# PlanktoscopeHat-v0_2-fab.net
KiCad netlist of a schematic drawn in EAGLE
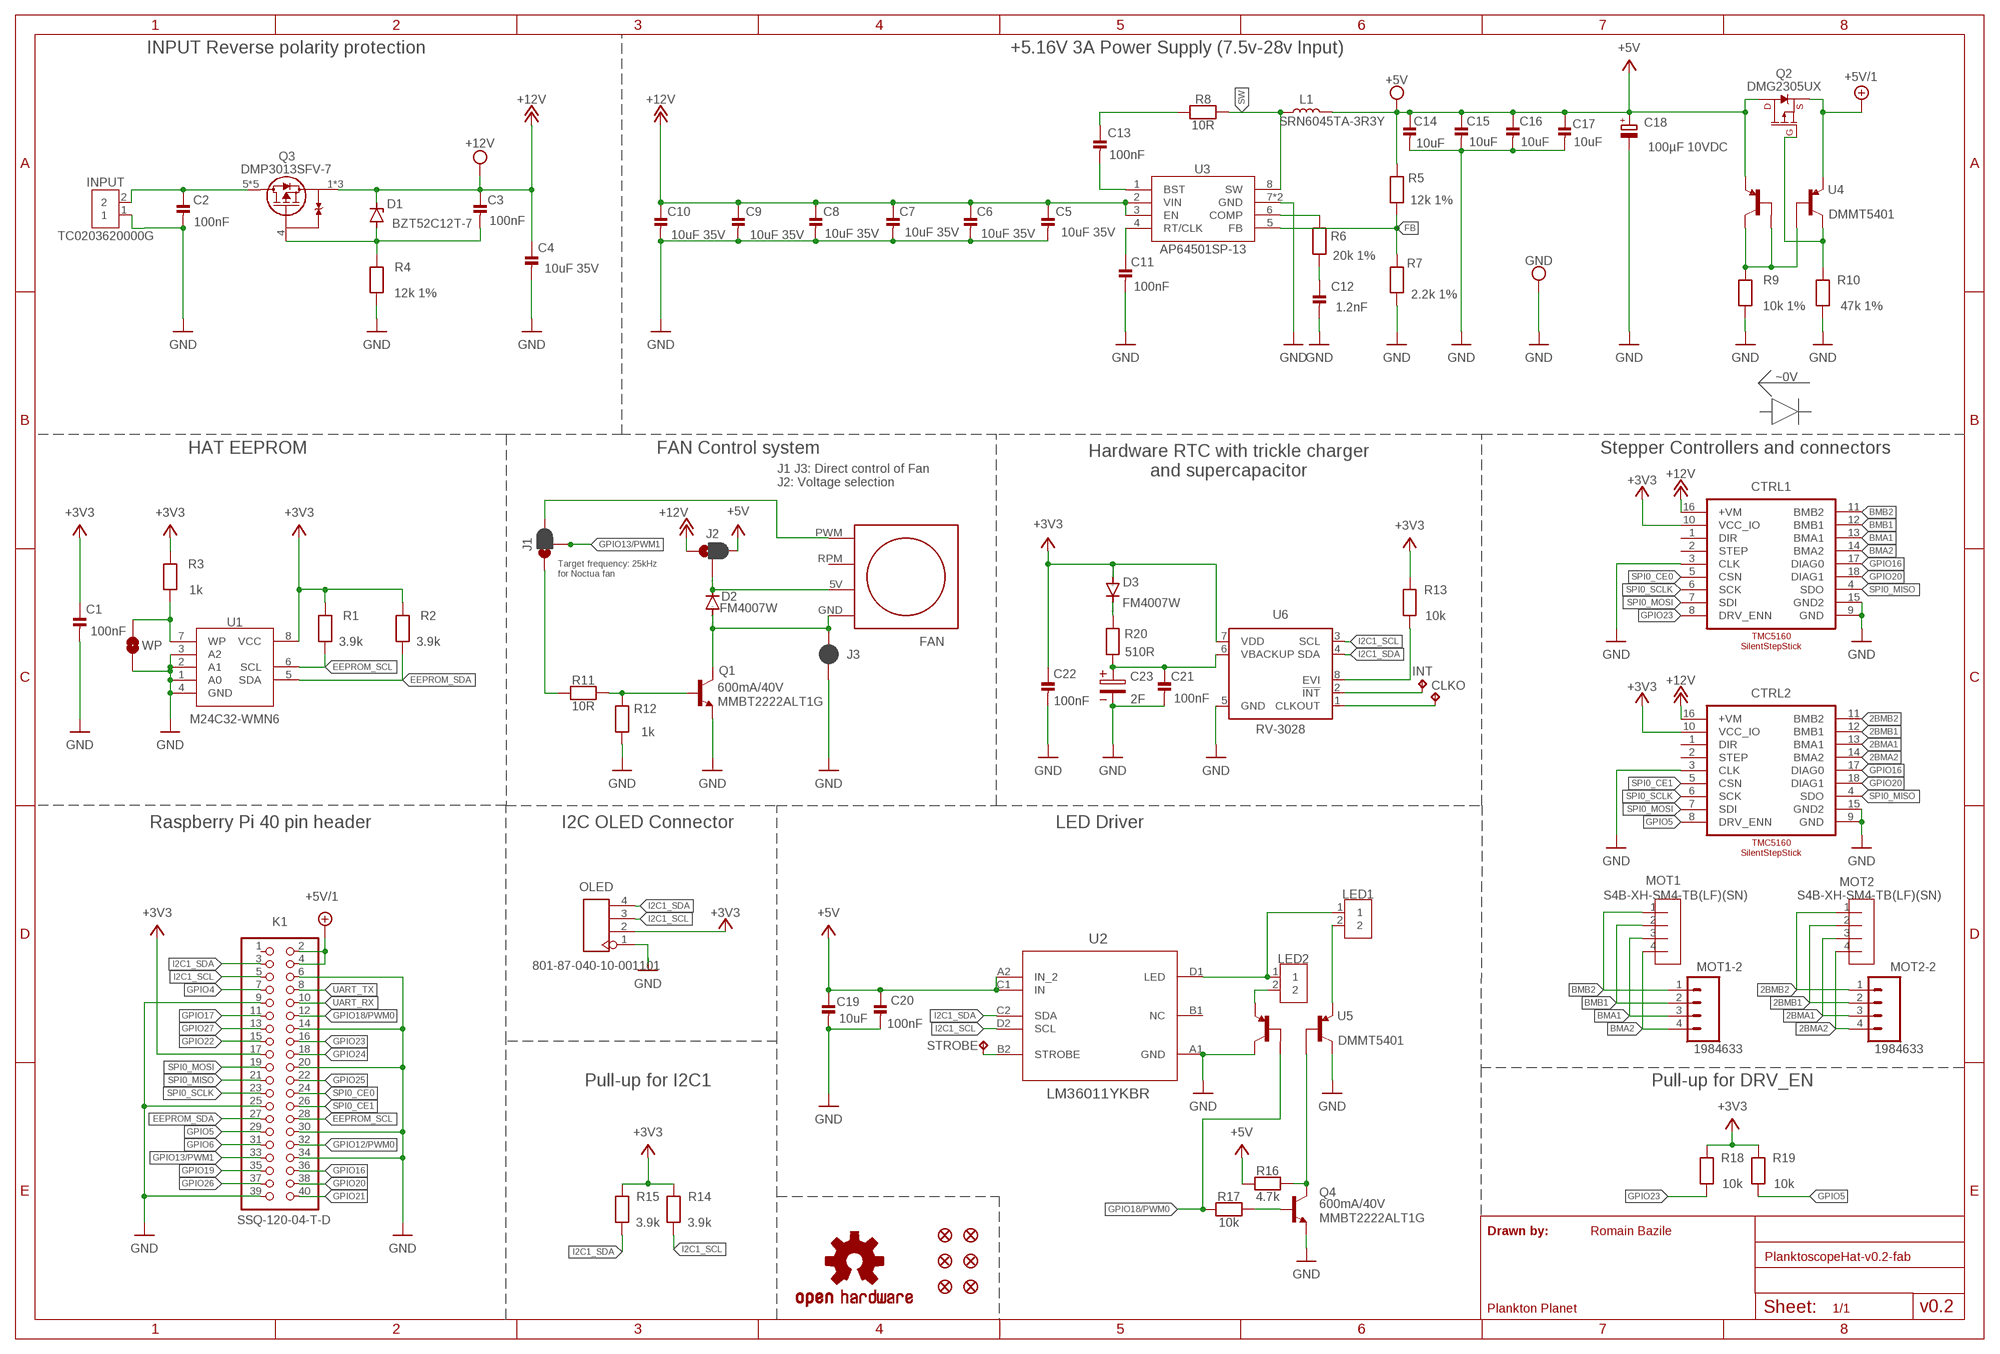
[diagram p0: schematic, sheet 1]

(export (version "E")
  (design (tool "Eeschema 10.0.6"))
  (components
    (comp (ref "+5V")
      (value "TESTPOINTPAD2MM")
      (footprint "eagle-import:TESTPOINT_PAD_2MM")
      (libsource (lib "eagle-import") (part "TESTPOINTPAD2MM"))
    )
    (comp (ref "+12V")
      (value "TESTPOINTPAD2MM")
      (footprint "eagle-import:TESTPOINT_PAD_2MM")
      (libsource (lib "eagle-import") (part "TESTPOINTPAD2MM"))
    )
    (comp (ref "C1")
      (value "100nF")
      (footprint "eagle-import:_0805MP")
      (libsource (lib "eagle-import") (part "CAP_CERAMIC_0805MP"))
    )
    (comp (ref "C2")
      (value "100nF")
      (footprint "eagle-import:_0805MP")
      (libsource (lib "eagle-import") (part "CAP_CERAMIC_0805MP"))
    )
    (comp (ref "C3")
      (value "100nF")
      (footprint "eagle-import:_0805MP")
      (libsource (lib "eagle-import") (part "CAP_CERAMIC_0805MP"))
    )
    (comp (ref "C4")
      (value "10uF 35V")
      (footprint "eagle-import:_0805MP")
      (libsource (lib "eagle-import") (part "CAP_CERAMIC_0805MP"))
    )
    (comp (ref "C5")
      (value "10uF 35V")
      (footprint "eagle-import:_0805MP")
      (libsource (lib "eagle-import") (part "CAP_CERAMIC_0805MP"))
    )
    (comp (ref "C6")
      (value "10uF 35V")
      (footprint "eagle-import:_0805MP")
      (libsource (lib "eagle-import") (part "CAP_CERAMIC_0805MP"))
    )
    (comp (ref "C7")
      (value "10uF 35V")
      (footprint "eagle-import:_0805MP")
      (libsource (lib "eagle-import") (part "CAP_CERAMIC_0805MP"))
    )
    (comp (ref "C8")
      (value "10uF 35V")
      (footprint "eagle-import:_0805MP")
      (libsource (lib "eagle-import") (part "CAP_CERAMIC_0805MP"))
    )
    (comp (ref "C9")
      (value "10uF 35V")
      (footprint "eagle-import:_0805MP")
      (libsource (lib "eagle-import") (part "CAP_CERAMIC_0805MP"))
    )
    (comp (ref "C10")
      (value "10uF 35V")
      (footprint "eagle-import:_0805MP")
      (libsource (lib "eagle-import") (part "CAP_CERAMIC_0805MP"))
    )
    (comp (ref "C11")
      (value "100nF")
      (footprint "eagle-import:_0805MP")
      (libsource (lib "eagle-import") (part "CAP_CERAMIC_0805MP"))
    )
    (comp (ref "C12")
      (value "1.2nF")
      (footprint "eagle-import:_0805MP")
      (libsource (lib "eagle-import") (part "CAP_CERAMIC_0805MP"))
    )
    (comp (ref "C13")
      (value "100nF")
      (footprint "eagle-import:_0805MP")
      (libsource (lib "eagle-import") (part "CAP_CERAMIC_0805MP"))
    )
    (comp (ref "C14")
      (value "10uF")
      (footprint "eagle-import:_0805MP")
      (libsource (lib "eagle-import") (part "CAP_CERAMIC_0805MP"))
    )
    (comp (ref "C15")
      (value "10uF")
      (footprint "eagle-import:_0805MP")
      (libsource (lib "eagle-import") (part "CAP_CERAMIC_0805MP"))
    )
    (comp (ref "C16")
      (value "10uF")
      (footprint "eagle-import:_0805MP")
      (libsource (lib "eagle-import") (part "CAP_CERAMIC_0805MP"))
    )
    (comp (ref "C17")
      (value "10uF")
      (footprint "eagle-import:_0805MP")
      (libsource (lib "eagle-import") (part "CAP_CERAMIC_0805MP"))
    )
    (comp (ref "C18")
      (value "100µF 10VDC")
      (footprint "eagle-import:CAPMP6032X280N")
      (fields (field (name "MPN") "TPSC107K010T0200"))
      (libsource (lib "eagle-import") (part "C-POLTANTALUM-2412(6032-METRIC)_"))
    )
    (comp (ref "C19")
      (value "10uF")
      (footprint "eagle-import:_0805MP")
      (libsource (lib "eagle-import") (part "CAP_CERAMIC_0805MP"))
    )
    (comp (ref "C20")
      (value "100nF")
      (footprint "eagle-import:_0805MP")
      (libsource (lib "eagle-import") (part "CAP_CERAMIC_0805MP"))
    )
    (comp (ref "C21")
      (value "100nF")
      (footprint "eagle-import:_0805MP")
      (libsource (lib "eagle-import") (part "CAP_CERAMIC_0805MP"))
    )
    (comp (ref "C22")
      (value "100nF")
      (footprint "eagle-import:_0805MP")
      (libsource (lib "eagle-import") (part "CAP_CERAMIC_0805MP"))
    )
    (comp (ref "C23")
      (value "2F")
      (footprint "eagle-import:8X3.5X0.9(DXAXB)")
      (fields (field (name "MPN") "SCCR12E105SRB"))
      (libsource (lib "eagle-import") (part "WCAP-PTHT_870135174001_8X8"))
    )
    (comp (ref "CLKO")
      (value "TPB1,27")
      (footprint "eagle-import:B1,27")
      (libsource (lib "eagle-import") (part "TPB1,27"))
    )
    (comp (ref "CTRL1")
      (value "TMC5160_SILENTSTEPSTICK")
      (footprint "eagle-import:TMC5160_STEPSTICK")
      (libsource (lib "eagle-import") (part "TMC5160_SILENTSTEPSTICK"))
    )
    (comp (ref "CTRL2")
      (value "TMC5160_SILENTSTEPSTICK")
      (footprint "eagle-import:TMC5160_STEPSTICK")
      (libsource (lib "eagle-import") (part "TMC5160_SILENTSTEPSTICK"))
    )
    (comp (ref "D1")
      (value "BZT52C12T-7")
      (footprint "eagle-import:SODFL1608X70")
      (libsource (lib "eagle-import") (part "ZENERSODFL(1608-METRIC)_"))
    )
    (comp (ref "D2")
      (value "FM4007W")
      (footprint "eagle-import:DO-214AC")
      (libsource (lib "eagle-import") (part "DIODE-DO-214AC"))
    )
    (comp (ref "D3")
      (value "FM4007W")
      (footprint "eagle-import:DO-214AC")
      (libsource (lib "eagle-import") (part "DIODE-DO-214AC"))
    )
    (comp (ref "FAN")
      (value "40MM_FAN")
      (footprint "eagle-import:40MM_FAN")
      (libsource (lib "eagle-import") (part "40MM_FAN"))
    )
    (comp (ref "FD1")
      (value "FIDUCIAL1X2")
      (footprint "eagle-import:FIDUCIAL-1X2")
      (libsource (lib "eagle-import") (part "FIDUCIAL1X2"))
    )
    (comp (ref "FD2")
      (value "FIDUCIAL1X2")
      (footprint "eagle-import:FIDUCIAL-1X2")
      (libsource (lib "eagle-import") (part "FIDUCIAL1X2"))
    )
    (comp (ref "FD3")
      (value "FIDUCIAL1X2")
      (footprint "eagle-import:FIDUCIAL-1X2")
      (libsource (lib "eagle-import") (part "FIDUCIAL1X2"))
    )
    (comp (ref "FD4")
      (value "FIDUCIAL1X2")
      (footprint "eagle-import:FIDUCIAL-1X2")
      (libsource (lib "eagle-import") (part "FIDUCIAL1X2"))
    )
    (comp (ref "FD5")
      (value "FIDUCIAL1X2")
      (footprint "eagle-import:FIDUCIAL-1X2")
      (libsource (lib "eagle-import") (part "FIDUCIAL1X2"))
    )
    (comp (ref "FD6")
      (value "FIDUCIAL1X2")
      (footprint "eagle-import:FIDUCIAL-1X2")
      (libsource (lib "eagle-import") (part "FIDUCIAL1X2"))
    )
    (comp (ref "GND")
      (value "TESTPOINTPAD2MM")
      (footprint "eagle-import:TESTPOINT_PAD_2MM")
      (libsource (lib "eagle-import") (part "TESTPOINTPAD2MM"))
    )
    (comp (ref "INPUT")
      (value "TC0203620000G")
      (footprint "eagle-import:TERMBLK_508-2N")
      (fields
        (field (name "MANUFACTURER") "TE Connectivity")
        (field (name "MPN") "282837-2")
        (field (name "MPN_1") "TC0203620000G")
      )
      (libsource (lib "eagle-import") (part "2828XX-2282837-2"))
    )
    (comp (ref "INT")
      (value "TPB1,27")
      (footprint "eagle-import:B1,27")
      (libsource (lib "eagle-import") (part "TPB1,27"))
    )
    (comp (ref "J1")
      (value "JUMPER-SMT_3_1-NC_PASTE_SILK")
      (footprint "eagle-import:SMT-JUMPER_3_1-NC_PASTE_SILK")
      (libsource (lib "eagle-import") (part "JUMPER-SMT_3_1-NC_PASTE_SILK"))
    )
    (comp (ref "J2")
      (value "JUMPER-SMT_3_1-NC_PASTE_SILK")
      (footprint "eagle-import:SMT-JUMPER_3_1-NC_PASTE_SILK")
      (libsource (lib "eagle-import") (part "JUMPER-SMT_3_1-NC_PASTE_SILK"))
    )
    (comp (ref "J3")
      (value "JUMPER-SMT_2_NC_PASTE_SILK")
      (footprint "eagle-import:SMT-JUMPER_2_NC_PASTE_SILK")
      (libsource (lib "eagle-import") (part "JUMPER-SMT_2_NC_PASTE_SILK"))
    )
    (comp (ref "K1")
      (value "SSQ-120-04-T-D")
      (footprint "eagle-import:2X20")
      (libsource (lib "eagle-import") (part "PINHD-2X20"))
    )
    (comp (ref "L1")
      (value "SRN6045TA-3R3Y")
      (footprint "eagle-import:SRN6045")
      (libsource (lib "eagle-import") (part "INDUCTOR-SRN6045-33UH"))
    )
    (comp (ref "LED1")
      (value "2828XX-2282834-2")
      (footprint "eagle-import:TERMBLK_254-2N")
      (libsource (lib "eagle-import") (part "2828XX-2282834-2"))
    )
    (comp (ref "LED2")
      (value "2828XX-2282834-2")
      (footprint "eagle-import:TERMBLK_254-2N")
      (libsource (lib "eagle-import") (part "2828XX-2282834-2"))
    )
    (comp (ref "LOGO1")
      (value "OSHW-LOGOL")
      (footprint "eagle-import:OSHW-LOGO-L")
      (libsource (lib "eagle-import") (part "OSHW-LOGOL"))
    )
    (comp (ref "MOT1")
      (value "S4B-XH-SM4-TB(LF)(SN)")
      (footprint "eagle-import:CONN_S4B-XH-SM4-TB_JST")
      (fields
        (field (name "MPN") "S4B-XH-SM4-TB(LF)(SN)")
        (field (name "COPYRIGHT") "Copyright (C) 2018 Accelerated Designs. All rights reserved")
      )
      (libsource (lib "eagle-import") (part "S4B-XH-SM4-TB(LF)(SN)"))
    )
    (comp (ref "MOT1-2")
      (value "1984633")
      (footprint "eagle-import:SCREWTERMINAL-3.5MM-4")
      (libsource (lib "eagle-import") (part "CONN_04SCREW"))
    )
    (comp (ref "MOT2")
      (value "S4B-XH-SM4-TB(LF)(SN)")
      (footprint "eagle-import:CONN_S4B-XH-SM4-TB_JST")
      (fields
        (field (name "MPN") "S4B-XH-SM4-TB(LF)(SN)")
        (field (name "COPYRIGHT") "Copyright (C) 2018 Accelerated Designs. All rights reserved")
      )
      (libsource (lib "eagle-import") (part "S4B-XH-SM4-TB(LF)(SN)"))
    )
    (comp (ref "MOT2-2")
      (value "1984633")
      (footprint "eagle-import:SCREWTERMINAL-3.5MM-4")
      (libsource (lib "eagle-import") (part "CONN_04SCREW"))
    )
    (comp (ref "OLED")
      (value "801-87-040-10-001101")
      (footprint "eagle-import:H4-2.54")
      (fields (field (name "MPN") "P125-1104A0BS116A1"))
      (libsource (lib "eagle-import") (part "DIP-BLACK-MALE-HEADER-VERT(4P-2.54)"))
    )
    (comp (ref "Q1")
      (value "600mA/40V")
      (footprint "eagle-import:SOT23-3")
      (fields (field (name "MPN") "MMBT2222ALT1G"))
      (libsource (lib "eagle-import") (part "TRANS_NPN-MMBT2222AL"))
    )
    (comp (ref "Q2")
      (value "DMG2305UX")
      (footprint "eagle-import:SOT23-3")
      (libsource (lib "eagle-import") (part "MOSFET_PCH-DMG2305UX-7"))
    )
    (comp (ref "Q3")
      (value "DMP3013SFV-7")
      (footprint "eagle-import:POWERDI3333-8_UX_DIO")
      (fields (field (name "COPYRIGHT") "Copyright (C) 2018 Accelerated Designs. All rights reserved"))
      (libsource (lib "eagle-import") (part "DMP3013SFV-7"))
    )
    (comp (ref "Q4")
      (value "600mA/40V")
      (footprint "eagle-import:SOT23-3")
      (fields (field (name "MPN") "MMBT2222ALT1G"))
      (libsource (lib "eagle-import") (part "TRANS_NPN-MMBT2222AL"))
    )
    (comp (ref "R1")
      (value "3.9k")
      (footprint "eagle-import:_0805MP")
      (libsource (lib "eagle-import") (part "RESISTOR_0805MP"))
    )
    (comp (ref "R2")
      (value "3.9k")
      (footprint "eagle-import:_0805MP")
      (libsource (lib "eagle-import") (part "RESISTOR_0805MP"))
    )
    (comp (ref "R3")
      (value "1k")
      (footprint "eagle-import:_0805MP")
      (libsource (lib "eagle-import") (part "RESISTOR_0805MP"))
    )
    (comp (ref "R4")
      (value "12k 1%")
      (footprint "eagle-import:_0805MP")
      (libsource (lib "eagle-import") (part "RESISTOR_0805MP"))
    )
    (comp (ref "R5")
      (value "12k 1%")
      (footprint "eagle-import:_0805MP")
      (libsource (lib "eagle-import") (part "RESISTOR_0805MP"))
    )
    (comp (ref "R6")
      (value "20k 1%")
      (footprint "eagle-import:_0805MP")
      (libsource (lib "eagle-import") (part "RESISTOR_0805MP"))
    )
    (comp (ref "R7")
      (value "2.2k 1%")
      (footprint "eagle-import:_0805MP")
      (libsource (lib "eagle-import") (part "RESISTOR_0805MP"))
    )
    (comp (ref "R8")
      (value "10R")
      (footprint "eagle-import:_0805MP")
      (libsource (lib "eagle-import") (part "RESISTOR_0805MP"))
    )
    (comp (ref "R9")
      (value "10k 1%")
      (footprint "eagle-import:_0805MP")
      (libsource (lib "eagle-import") (part "RESISTOR_0805MP"))
    )
    (comp (ref "R10")
      (value "47k 1%")
      (footprint "eagle-import:_0805MP")
      (libsource (lib "eagle-import") (part "RESISTOR_0805MP"))
    )
    (comp (ref "R11")
      (value "10R")
      (footprint "eagle-import:_0805MP")
      (libsource (lib "eagle-import") (part "RESISTOR_0805MP"))
    )
    (comp (ref "R12")
      (value "1k")
      (footprint "eagle-import:_0805MP")
      (libsource (lib "eagle-import") (part "RESISTOR_0805MP"))
    )
    (comp (ref "R13")
      (value "10k")
      (footprint "eagle-import:_0805MP")
      (libsource (lib "eagle-import") (part "RESISTOR_0805MP"))
    )
    (comp (ref "R14")
      (value "3.9k")
      (footprint "eagle-import:_0805MP")
      (libsource (lib "eagle-import") (part "RESISTOR_0805MP"))
    )
    (comp (ref "R15")
      (value "3.9k")
      (footprint "eagle-import:_0805MP")
      (libsource (lib "eagle-import") (part "RESISTOR_0805MP"))
    )
    (comp (ref "R16")
      (value "4.7k")
      (footprint "eagle-import:_0805MP")
      (libsource (lib "eagle-import") (part "RESISTOR_0805MP"))
    )
    (comp (ref "R17")
      (value "10k")
      (footprint "eagle-import:_0805MP")
      (libsource (lib "eagle-import") (part "RESISTOR_0805MP"))
    )
    (comp (ref "R18")
      (value "10k")
      (footprint "eagle-import:_0805MP")
      (libsource (lib "eagle-import") (part "RESISTOR_0805MP"))
    )
    (comp (ref "R19")
      (value "10k")
      (footprint "eagle-import:_0805MP")
      (libsource (lib "eagle-import") (part "RESISTOR_0805MP"))
    )
    (comp (ref "R20")
      (value "510R")
      (footprint "eagle-import:_0805MP")
      (libsource (lib "eagle-import") (part "RESISTOR_0805MP"))
    )
    (comp (ref "STROBE")
      (value "TPTP15R")
      (footprint "eagle-import:TP15R")
      (libsource (lib "eagle-import") (part "TPTP15R"))
    )
    (comp (ref "U1")
      (value "M24C32-WMN6")
      (footprint "eagle-import:SO-8_STM")
      (libsource (lib "eagle-import") (part "M24C32-WMN6"))
    )
    (comp (ref "U2")
      (value "LM36011YKBR")
      (footprint "eagle-import:YKB0008AGAG")
      (fields (field (name "MANUFACTURER") "Texas Instruments"))
      (libsource (lib "eagle-import") (part "LM36011YKBR"))
    )
    (comp (ref "U3")
      (value "AP64501SP-13")
      (footprint "eagle-import:SO-8EP_DIO")
      (fields
        (field (name "MANUFACTURER_PART_NUMBER") "AP64500SP-13")
        (field (name "COPYRIGHT") "Copyright (C) 2018 Accelerated Designs. All rights reserved")
      )
      (libsource (lib "eagle-import") (part "AP64500SP-13"))
    )
    (comp (ref "U4")
      (value "DMMT5401")
      (footprint "eagle-import:SOT26")
      (libsource (lib "eagle-import") (part "DDMT5401"))
    )
    (comp (ref "U5")
      (value "DMMT5401")
      (footprint "eagle-import:SOT26")
      (libsource (lib "eagle-import") (part "DDMT5401"))
    )
    (comp (ref "U6")
      (value "RV-3028")
      (footprint "eagle-import:RV-3028")
      (libsource (lib "eagle-import") (part "RV-3028"))
    )
    (comp (ref "WP")
      (value "JUMPER-SMT_2_NO_SILK")
      (footprint "eagle-import:SMT-JUMPER_2_NO_SILK")
      (libsource (lib "eagle-import") (part "JUMPER-SMT_2_NO_SILK"))
    )
  )
  (nets
    (net (code "1") (name "+3V3") (class "Default")
      (node (ref "C1") (pin "1") (pinfunction "1_1") (pintype "passive"))
      (node (ref "C22") (pin "1") (pinfunction "1_1") (pintype "passive"))
      (node (ref "CTRL1") (pin "10") (pinfunction "VCC_IO_10") (pintype "passive"))
      (node (ref "CTRL2") (pin "10") (pinfunction "VCC_IO_10") (pintype "passive"))
      (node (ref "D3") (pin "A") (pinfunction "A_A") (pintype "passive"))
      (node (ref "K1") (pin "17") (pinfunction "17_17") (pintype "passive"))
      (node (ref "OLED") (pin "2") (pinfunction "P$2_2") (pintype "bidirectional"))
      (node (ref "R1") (pin "2") (pinfunction "2_2") (pintype "passive"))
      (node (ref "R13") (pin "2") (pinfunction "2_2") (pintype "passive"))
      (node (ref "R14") (pin "2") (pinfunction "2_2") (pintype "passive"))
      (node (ref "R15") (pin "2") (pinfunction "2_2") (pintype "passive"))
      (node (ref "R18") (pin "2") (pinfunction "2_2") (pintype "passive"))
      (node (ref "R19") (pin "2") (pinfunction "2_2") (pintype "passive"))
      (node (ref "R2") (pin "2") (pinfunction "2_2") (pintype "passive"))
      (node (ref "R3") (pin "2") (pinfunction "2_2") (pintype "passive"))
      (node (ref "U1") (pin "8") (pinfunction "VCC_8") (pintype "power_in"))
      (node (ref "U6") (pin "7") (pinfunction "VDD_7") (pintype "bidirectional"))
    )
    (net (code "2") (name "+5V") (class "Default")
      (node (ref "+5V") (pin "P$1") (pinfunction "P$1_P$1") (pintype "bidirectional"))
      (node (ref "C14") (pin "1") (pinfunction "1_1") (pintype "passive"))
      (node (ref "C15") (pin "1") (pinfunction "1_1") (pintype "passive"))
      (node (ref "C16") (pin "1") (pinfunction "1_1") (pintype "passive"))
      (node (ref "C17") (pin "1") (pinfunction "1_1") (pintype "passive"))
      (node (ref "C18") (pin "1") (pinfunction "+_1") (pintype "passive"))
      (node (ref "C19") (pin "1") (pinfunction "1_1") (pintype "passive"))
      (node (ref "C20") (pin "1") (pinfunction "1_1") (pintype "passive"))
      (node (ref "J2") (pin "3") (pinfunction "3_3") (pintype "passive"))
      (node (ref "L1") (pin "2") (pinfunction "2_2") (pintype "passive"))
      (node (ref "Q2") (pin "3") (pinfunction "D_3") (pintype "bidirectional"))
      (node (ref "R16") (pin "2") (pinfunction "2_2") (pintype "passive"))
      (node (ref "R5") (pin "2") (pinfunction "2_2") (pintype "passive"))
      (node (ref "U2") (pin "A2") (pinfunction "IN_2_A2") (pintype "power_in"))
      (node (ref "U2") (pin "C1") (pinfunction "IN_C1") (pintype "power_in"))
      (node (ref "U4") (pin "D1") (pinfunction "6_D1") (pintype "passive"))
    )
    (net (code "3") (name "+5V{slash}1") (class "Default")
      (node (ref "K1") (pin "2") (pinfunction "2_2") (pintype "passive"))
      (node (ref "K1") (pin "4") (pinfunction "4_4") (pintype "passive"))
      (node (ref "Q2") (pin "2") (pinfunction "S_2") (pintype "bidirectional"))
      (node (ref "U4") (pin "S1") (pinfunction "5_S1") (pintype "passive"))
    )
    (net (code "4") (name "+12V") (class "Default")
      (node (ref "+12V") (pin "P$1") (pinfunction "P$1_P$1") (pintype "bidirectional"))
      (node (ref "C10") (pin "1") (pinfunction "1_1") (pintype "passive"))
      (node (ref "C3") (pin "1") (pinfunction "1_1") (pintype "passive"))
      (node (ref "C4") (pin "1") (pinfunction "1_1") (pintype "passive"))
      (node (ref "C5") (pin "1") (pinfunction "1_1") (pintype "passive"))
      (node (ref "C6") (pin "1") (pinfunction "1_1") (pintype "passive"))
      (node (ref "C7") (pin "1") (pinfunction "1_1") (pintype "passive"))
      (node (ref "C8") (pin "1") (pinfunction "1_1") (pintype "passive"))
      (node (ref "C9") (pin "1") (pinfunction "1_1") (pintype "passive"))
      (node (ref "CTRL1") (pin "16") (pinfunction "+VM_16") (pintype "passive"))
      (node (ref "CTRL2") (pin "16") (pinfunction "+VM_16") (pintype "passive"))
      (node (ref "D1") (pin "1") (pinfunction "C_1") (pintype "passive"))
      (node (ref "J2") (pin "1") (pinfunction "1_1") (pintype "passive"))
      (node (ref "Q3") (pin "1") (pinfunction "S_1") (pintype "passive"))
      (node (ref "Q3") (pin "2") (pinfunction "S_2") (pintype "passive"))
      (node (ref "Q3") (pin "3") (pinfunction "S_3") (pintype "passive"))
      (node (ref "U3") (pin "2") (pinfunction "VIN_2") (pintype "power_in"))
      (node (ref "U3") (pin "3") (pinfunction "EN_3") (pintype "input"))
    )
    (net (code "5") (name "2BMA1") (class "Default")
      (node (ref "CTRL2") (pin "13") (pinfunction "BMA1_13") (pintype "passive"))
      (node (ref "MOT2") (pin "3") (pinfunction "3_3") (pintype "passive"))
      (node (ref "MOT2-2") (pin "3") (pinfunction "3_3") (pintype "passive"))
    )
    (net (code "6") (name "2BMA2") (class "Default")
      (node (ref "CTRL2") (pin "14") (pinfunction "BMA2_14") (pintype "passive"))
      (node (ref "MOT2") (pin "4") (pinfunction "4_4") (pintype "passive"))
      (node (ref "MOT2-2") (pin "4") (pinfunction "4_4") (pintype "passive"))
    )
    (net (code "7") (name "2BMB1") (class "Default")
      (node (ref "CTRL2") (pin "12") (pinfunction "BMB1_12") (pintype "passive"))
      (node (ref "MOT2") (pin "2") (pinfunction "2_2") (pintype "passive"))
      (node (ref "MOT2-2") (pin "2") (pinfunction "2_2") (pintype "passive"))
    )
    (net (code "8") (name "2BMB2") (class "Default")
      (node (ref "CTRL2") (pin "11") (pinfunction "BMB2_11") (pintype "passive"))
      (node (ref "MOT2") (pin "1") (pinfunction "1_1") (pintype "passive"))
      (node (ref "MOT2-2") (pin "1") (pinfunction "1_1") (pintype "passive"))
    )
    (net (code "9") (name "BMA1") (class "Default")
      (node (ref "CTRL1") (pin "13") (pinfunction "BMA1_13") (pintype "passive"))
      (node (ref "MOT1") (pin "3") (pinfunction "3_3") (pintype "passive"))
      (node (ref "MOT1-2") (pin "3") (pinfunction "3_3") (pintype "passive"))
    )
    (net (code "10") (name "BMA2") (class "Default")
      (node (ref "CTRL1") (pin "14") (pinfunction "BMA2_14") (pintype "passive"))
      (node (ref "MOT1") (pin "4") (pinfunction "4_4") (pintype "passive"))
      (node (ref "MOT1-2") (pin "4") (pinfunction "4_4") (pintype "passive"))
    )
    (net (code "11") (name "BMB1") (class "Default")
      (node (ref "CTRL1") (pin "12") (pinfunction "BMB1_12") (pintype "passive"))
      (node (ref "MOT1") (pin "2") (pinfunction "2_2") (pintype "passive"))
      (node (ref "MOT1-2") (pin "2") (pinfunction "2_2") (pintype "passive"))
    )
    (net (code "12") (name "BMB2") (class "Default")
      (node (ref "CTRL1") (pin "11") (pinfunction "BMB2_11") (pintype "passive"))
      (node (ref "MOT1") (pin "1") (pinfunction "1_1") (pintype "passive"))
      (node (ref "MOT1-2") (pin "1") (pinfunction "1_1") (pintype "passive"))
    )
    (net (code "13") (name "EEPROM_SCL") (class "Default")
      (node (ref "K1") (pin "28") (pinfunction "28_28") (pintype "passive"))
      (node (ref "R1") (pin "1") (pinfunction "1_1") (pintype "passive"))
      (node (ref "U1") (pin "6") (pinfunction "SCL_6") (pintype "input"))
    )
    (net (code "14") (name "EEPROM_SDA") (class "Default")
      (node (ref "K1") (pin "27") (pinfunction "27_27") (pintype "passive"))
      (node (ref "R2") (pin "1") (pinfunction "1_1") (pintype "passive"))
      (node (ref "U1") (pin "5") (pinfunction "SDA_5") (pintype "bidirectional"))
    )
    (net (code "15") (name "FB") (class "Default")
      (node (ref "R5") (pin "1") (pinfunction "1_1") (pintype "passive"))
      (node (ref "R7") (pin "2") (pinfunction "2_2") (pintype "passive"))
      (node (ref "U3") (pin "5") (pinfunction "FB_5") (pintype "passive"))
    )
    (net (code "16") (name "GND") (class "Default")
      (node (ref "C1") (pin "2") (pinfunction "2_2") (pintype "passive"))
      (node (ref "C10") (pin "2") (pinfunction "2_2") (pintype "passive"))
      (node (ref "C11") (pin "2") (pinfunction "2_2") (pintype "passive"))
      (node (ref "C12") (pin "2") (pinfunction "2_2") (pintype "passive"))
      (node (ref "C14") (pin "2") (pinfunction "2_2") (pintype "passive"))
      (node (ref "C15") (pin "2") (pinfunction "2_2") (pintype "passive"))
      (node (ref "C16") (pin "2") (pinfunction "2_2") (pintype "passive"))
      (node (ref "C17") (pin "2") (pinfunction "2_2") (pintype "passive"))
      (node (ref "C18") (pin "2") (pinfunction "-_2") (pintype "passive"))
      (node (ref "C19") (pin "2") (pinfunction "2_2") (pintype "passive"))
      (node (ref "C2") (pin "2") (pinfunction "2_2") (pintype "passive"))
      (node (ref "C20") (pin "2") (pinfunction "2_2") (pintype "passive"))
      (node (ref "C21") (pin "2") (pinfunction "2_2") (pintype "passive"))
      (node (ref "C22") (pin "2") (pinfunction "2_2") (pintype "passive"))
      (node (ref "C23") (pin "2") (pinfunction "2_2") (pintype "passive"))
      (node (ref "C4") (pin "2") (pinfunction "2_2") (pintype "passive"))
      (node (ref "C5") (pin "2") (pinfunction "2_2") (pintype "passive"))
      (node (ref "C6") (pin "2") (pinfunction "2_2") (pintype "passive"))
      (node (ref "C7") (pin "2") (pinfunction "2_2") (pintype "passive"))
      (node (ref "C8") (pin "2") (pinfunction "2_2") (pintype "passive"))
      (node (ref "C9") (pin "2") (pinfunction "2_2") (pintype "passive"))
      (node (ref "CTRL1") (pin "15") (pinfunction "GND2_15") (pintype "passive"))
      (node (ref "CTRL1") (pin "3") (pinfunction "CLK_3") (pintype "passive"))
      (node (ref "CTRL1") (pin "9") (pinfunction "GND_9") (pintype "passive"))
      (node (ref "CTRL2") (pin "15") (pinfunction "GND2_15") (pintype "passive"))
      (node (ref "CTRL2") (pin "3") (pinfunction "CLK_3") (pintype "passive"))
      (node (ref "CTRL2") (pin "9") (pinfunction "GND_9") (pintype "passive"))
      (node (ref "GND") (pin "P$1") (pinfunction "P$1_P$1") (pintype "bidirectional"))
      (node (ref "INPUT") (pin "1") (pinfunction "1_1") (pintype "bidirectional"))
      (node (ref "J3") (pin "1") (pinfunction "1_1") (pintype "passive"))
      (node (ref "K1") (pin "14") (pinfunction "14_14") (pintype "passive"))
      (node (ref "K1") (pin "20") (pinfunction "20_20") (pintype "passive"))
      (node (ref "K1") (pin "25") (pinfunction "25_25") (pintype "passive"))
      (node (ref "K1") (pin "30") (pinfunction "30_30") (pintype "passive"))
      (node (ref "K1") (pin "34") (pinfunction "34_34") (pintype "passive"))
      (node (ref "K1") (pin "39") (pinfunction "39_39") (pintype "passive"))
      (node (ref "K1") (pin "6") (pinfunction "6_6") (pintype "passive"))
      (node (ref "K1") (pin "9") (pinfunction "9_9") (pintype "passive"))
      (node (ref "OLED") (pin "1") (pinfunction "P$1_1") (pintype "bidirectional"))
      (node (ref "Q1") (pin "2") (pinfunction "E_2") (pintype "passive"))
      (node (ref "Q4") (pin "2") (pinfunction "E_2") (pintype "passive"))
      (node (ref "R10") (pin "1") (pinfunction "1_1") (pintype "passive"))
      (node (ref "R12") (pin "1") (pinfunction "1_1") (pintype "passive"))
      (node (ref "R4") (pin "1") (pinfunction "1_1") (pintype "passive"))
      (node (ref "R7") (pin "1") (pinfunction "1_1") (pintype "passive"))
      (node (ref "R9") (pin "1") (pinfunction "1_1") (pintype "passive"))
      (node (ref "U1") (pin "1") (pinfunction "A0_1") (pintype "input"))
      (node (ref "U1") (pin "2") (pinfunction "A1_2") (pintype "input"))
      (node (ref "U1") (pin "3") (pinfunction "A2_3") (pintype "input"))
      (node (ref "U1") (pin "4") (pinfunction "GND_4") (pintype "power_in"))
      (node (ref "U2") (pin "A1") (pinfunction "GND_A1") (pintype "power_in"))
      (node (ref "U3") (pin "7") (pinfunction "GND_7") (pintype "passive"))
      (node (ref "U3") (pin "EPAD") (pinfunction "GND_EPAD") (pintype "passive"))
      (node (ref "U5") (pin "D2") (pinfunction "4_D2") (pintype "passive"))
      (node (ref "U5") (pin "G1") (pinfunction "1_G1") (pintype "passive"))
      (node (ref "U6") (pin "5") (pinfunction "GND_5") (pintype "bidirectional"))
      (node (ref "WP") (pin "1") (pinfunction "1_1") (pintype "passive"))
    )
    (net (code "17") (name "GPIO4") (class "Default")
      (node (ref "K1") (pin "7") (pinfunction "7_7") (pintype "passive"))
    )
    (net (code "18") (name "GPIO5") (class "Default")
      (node (ref "CTRL2") (pin "8") (pinfunction "DRV_ENN_8") (pintype "passive"))
      (node (ref "K1") (pin "29") (pinfunction "29_29") (pintype "passive"))
      (node (ref "R19") (pin "1") (pinfunction "1_1") (pintype "passive"))
    )
    (net (code "19") (name "GPIO6") (class "Default")
      (node (ref "K1") (pin "31") (pinfunction "31_31") (pintype "passive"))
    )
    (net (code "20") (name "GPIO12{slash}PWM0") (class "Default")
      (node (ref "K1") (pin "32") (pinfunction "32_32") (pintype "passive"))
    )
    (net (code "21") (name "GPIO13{slash}PWM1") (class "Default")
      (node (ref "J1") (pin "2") (pinfunction "2_2") (pintype "passive"))
      (node (ref "K1") (pin "33") (pinfunction "33_33") (pintype "passive"))
    )
    (net (code "22") (name "GPIO16") (class "Default")
      (node (ref "CTRL1") (pin "17") (pinfunction "DIAG0_17") (pintype "passive"))
      (node (ref "CTRL2") (pin "17") (pinfunction "DIAG0_17") (pintype "passive"))
      (node (ref "K1") (pin "36") (pinfunction "36_36") (pintype "passive"))
    )
    (net (code "23") (name "GPIO17") (class "Default")
      (node (ref "K1") (pin "11") (pinfunction "11_11") (pintype "passive"))
    )
    (net (code "24") (name "GPIO18{slash}PWM0") (class "Default")
      (node (ref "K1") (pin "12") (pinfunction "12_12") (pintype "passive"))
      (node (ref "R17") (pin "1") (pinfunction "1_1") (pintype "passive"))
      (node (ref "U5") (pin "S2") (pinfunction "2_S2") (pintype "passive"))
    )
    (net (code "25") (name "GPIO19") (class "Default")
      (node (ref "K1") (pin "35") (pinfunction "35_35") (pintype "passive"))
    )
    (net (code "26") (name "GPIO20") (class "Default")
      (node (ref "CTRL1") (pin "18") (pinfunction "DIAG1_18") (pintype "passive"))
      (node (ref "CTRL2") (pin "18") (pinfunction "DIAG1_18") (pintype "passive"))
      (node (ref "K1") (pin "38") (pinfunction "38_38") (pintype "passive"))
    )
    (net (code "27") (name "GPIO21") (class "Default")
      (node (ref "K1") (pin "40") (pinfunction "40_40") (pintype "passive"))
    )
    (net (code "28") (name "GPIO22") (class "Default")
      (node (ref "K1") (pin "15") (pinfunction "15_15") (pintype "passive"))
    )
    (net (code "29") (name "GPIO23") (class "Default")
      (node (ref "CTRL1") (pin "8") (pinfunction "DRV_ENN_8") (pintype "passive"))
      (node (ref "K1") (pin "16") (pinfunction "16_16") (pintype "passive"))
      (node (ref "R18") (pin "1") (pinfunction "1_1") (pintype "passive"))
    )
    (net (code "30") (name "GPIO24") (class "Default")
      (node (ref "K1") (pin "18") (pinfunction "18_18") (pintype "passive"))
    )
    (net (code "31") (name "GPIO25") (class "Default")
      (node (ref "K1") (pin "22") (pinfunction "22_22") (pintype "passive"))
    )
    (net (code "32") (name "GPIO26") (class "Default")
      (node (ref "K1") (pin "37") (pinfunction "37_37") (pintype "passive"))
    )
    (net (code "33") (name "GPIO27") (class "Default")
      (node (ref "K1") (pin "13") (pinfunction "13_13") (pintype "passive"))
    )
    (net (code "34") (name "I2C1_SCL") (class "Default")
      (node (ref "K1") (pin "5") (pinfunction "5_5") (pintype "passive"))
      (node (ref "OLED") (pin "3") (pinfunction "P$3_3") (pintype "bidirectional"))
      (node (ref "R14") (pin "1") (pinfunction "1_1") (pintype "passive"))
      (node (ref "U2") (pin "D2") (pinfunction "SCL_D2") (pintype "input"))
      (node (ref "U6") (pin "3") (pinfunction "SCL_3") (pintype "bidirectional"))
    )
    (net (code "35") (name "I2C1_SDA") (class "Default")
      (node (ref "K1") (pin "3") (pinfunction "3_3") (pintype "passive"))
      (node (ref "OLED") (pin "4") (pinfunction "P$4_4") (pintype "bidirectional"))
      (node (ref "R15") (pin "1") (pinfunction "1_1") (pintype "passive"))
      (node (ref "U2") (pin "C2") (pinfunction "SDA_C2") (pintype "bidirectional"))
      (node (ref "U6") (pin "4") (pinfunction "SDA_4") (pintype "bidirectional"))
    )
    (net (code "36") (name "Net-(C2-Pad1)") (class "Default")
      (node (ref "C2") (pin "1") (pinfunction "1_1") (pintype "passive"))
      (node (ref "INPUT") (pin "2") (pinfunction "2_2") (pintype "bidirectional"))
      (node (ref "Q3") (pin "5") (pinfunction "D_5") (pintype "passive"))
      (node (ref "Q3") (pin "6") (pinfunction "D_6") (pintype "passive"))
      (node (ref "Q3") (pin "7") (pinfunction "D_7") (pintype "passive"))
      (node (ref "Q3") (pin "8") (pinfunction "D_8") (pintype "passive"))
      (node (ref "Q3") (pin "9") (pinfunction "D_9") (pintype "passive"))
    )
    (net (code "37") (name "Net-(C12-Pad1)") (class "Default")
      (node (ref "C12") (pin "1") (pinfunction "1_1") (pintype "passive"))
      (node (ref "R6") (pin "1") (pinfunction "1_1") (pintype "passive"))
    )
    (net (code "38") (name "Net-(C13-Pad1)") (class "Default")
      (node (ref "C13") (pin "1") (pinfunction "1_1") (pintype "passive"))
      (node (ref "R8") (pin "2") (pinfunction "2_2") (pintype "passive"))
    )
    (net (code "39") (name "Net-(D1-A)") (class "Default")
      (node (ref "C3") (pin "2") (pinfunction "2_2") (pintype "passive"))
      (node (ref "D1") (pin "2") (pinfunction "A_2") (pintype "passive"))
      (node (ref "Q3") (pin "4") (pinfunction "G_4") (pintype "passive"))
      (node (ref "R4") (pin "2") (pinfunction "2_2") (pintype "passive"))
    )
    (net (code "40") (name "Net-(D3-PadC)") (class "Default")
      (node (ref "D3") (pin "C") (pinfunction "C_C") (pintype "passive"))
      (node (ref "R20") (pin "2") (pinfunction "2_2") (pintype "passive"))
    )
    (net (code "41") (name "Net-(FAN-+5V)") (class "Default")
      (node (ref "D2") (pin "C") (pinfunction "C_C") (pintype "passive"))
      (node (ref "FAN") (pin "5V") (pinfunction "+5V_5V") (pintype "passive"))
      (node (ref "J2") (pin "2") (pinfunction "2_2") (pintype "passive"))
    )
    (net (code "42") (name "Net-(FAN-PadPWM)") (class "Default")
      (node (ref "FAN") (pin "PWM") (pinfunction "PWM_PWM") (pintype "passive"))
      (node (ref "J1") (pin "3") (pinfunction "3_3") (pintype "passive"))
    )
    (net (code "43") (name "Net-(J1-Pad1)") (class "Default")
      (node (ref "J1") (pin "1") (pinfunction "1_1") (pintype "passive"))
      (node (ref "R11") (pin "1") (pinfunction "1_1") (pintype "passive"))
    )
    (net (code "44") (name "Net-(Q1-B)") (class "Default")
      (node (ref "Q1") (pin "1") (pinfunction "B_1") (pintype "passive"))
      (node (ref "R11") (pin "2") (pinfunction "2_2") (pintype "passive"))
      (node (ref "R12") (pin "2") (pinfunction "2_2") (pintype "passive"))
    )
    (net (code "45") (name "Net-(Q1-C)") (class "Default")
      (node (ref "D2") (pin "A") (pinfunction "A_A") (pintype "passive"))
      (node (ref "FAN") (pin "GND") (pinfunction "GND_GND") (pintype "passive"))
      (node (ref "J3") (pin "2") (pinfunction "2_2") (pintype "passive"))
      (node (ref "Q1") (pin "3") (pinfunction "C_3") (pintype "passive"))
    )
    (net (code "46") (name "Net-(Q2-G)") (class "Default")
      (node (ref "Q2") (pin "1") (pinfunction "G_1") (pintype "bidirectional"))
      (node (ref "R10") (pin "2") (pinfunction "2_2") (pintype "passive"))
      (node (ref "U4") (pin "D2") (pinfunction "4_D2") (pintype "passive"))
    )
    (net (code "47") (name "Net-(Q4-B)") (class "Default")
      (node (ref "Q4") (pin "1") (pinfunction "B_1") (pintype "passive"))
      (node (ref "R17") (pin "2") (pinfunction "2_2") (pintype "passive"))
    )
    (net (code "48") (name "Net-(Q4-C)") (class "Default")
      (node (ref "Q4") (pin "3") (pinfunction "C_3") (pintype "passive"))
      (node (ref "R16") (pin "1") (pinfunction "1_1") (pintype "passive"))
      (node (ref "U5") (pin "G2") (pinfunction "3_G2") (pintype "passive"))
    )
    (net (code "49") (name "Net-(U1-WP)") (class "Default")
      (node (ref "R3") (pin "1") (pinfunction "1_1") (pintype "passive"))
      (node (ref "U1") (pin "7") (pinfunction "WP_7") (pintype "input"))
      (node (ref "WP") (pin "2") (pinfunction "2_2") (pintype "passive"))
    )
    (net (code "50") (name "Net-(U2-LED)") (class "Default")
      (node (ref "LED1") (pin "1") (pinfunction "1_1") (pintype "bidirectional"))
      (node (ref "LED2") (pin "1") (pinfunction "1_1") (pintype "bidirectional"))
      (node (ref "U2") (pin "D1") (pinfunction "LED_D1") (pintype "power_in"))
    )
    (net (code "51") (name "Net-(U2-STROBE)") (class "Default")
      (node (ref "STROBE") (pin "TP") (pinfunction "TP_TP") (pintype "input"))
      (node (ref "U2") (pin "B2") (pinfunction "STROBE_B2") (pintype "input"))
    )
    (net (code "52") (name "Net-(U3-BST)") (class "Default")
      (node (ref "C13") (pin "2") (pinfunction "2_2") (pintype "passive"))
      (node (ref "U3") (pin "1") (pinfunction "BST_1") (pintype "power_in"))
    )
    (net (code "53") (name "Net-(U3-COMP)") (class "Default")
      (node (ref "R6") (pin "2") (pinfunction "2_2") (pintype "passive"))
      (node (ref "U3") (pin "6") (pinfunction "COMP_6") (pintype "passive"))
    )
    (net (code "54") (name "Net-(U3-RT{slash}CLK)") (class "Default")
      (node (ref "C11") (pin "1") (pinfunction "1_1") (pintype "passive"))
      (node (ref "U3") (pin "4") (pinfunction "RT/CLK_4") (pintype "passive"))
    )
    (net (code "55") (name "Net-(U4-1)") (class "Default")
      (node (ref "R9") (pin "2") (pinfunction "2_2") (pintype "passive"))
      (node (ref "U4") (pin "G1") (pinfunction "1_G1") (pintype "passive"))
      (node (ref "U4") (pin "G2") (pinfunction "3_G2") (pintype "passive"))
      (node (ref "U4") (pin "S2") (pinfunction "2_S2") (pintype "passive"))
    )
    (net (code "56") (name "Net-(U5-5)") (class "Default")
      (node (ref "LED1") (pin "2") (pinfunction "2_2") (pintype "bidirectional"))
      (node (ref "U5") (pin "S1") (pinfunction "5_S1") (pintype "passive"))
    )
    (net (code "57") (name "Net-(U5-6)") (class "Default")
      (node (ref "LED2") (pin "2") (pinfunction "2_2") (pintype "bidirectional"))
      (node (ref "U5") (pin "D1") (pinfunction "6_D1") (pintype "passive"))
    )
    (net (code "58") (name "Net-(U6-CLKOUT)") (class "Default")
      (node (ref "CLKO") (pin "TP") (pinfunction "TP_TP") (pintype "input"))
      (node (ref "U6") (pin "1") (pinfunction "CLKOUT_1") (pintype "bidirectional"))
    )
    (net (code "59") (name "Net-(U6-EVI)") (class "Default")
      (node (ref "R13") (pin "1") (pinfunction "1_1") (pintype "passive"))
      (node (ref "U6") (pin "8") (pinfunction "EVI_8") (pintype "bidirectional"))
    )
    (net (code "60") (name "Net-(U6-VBACKUP)") (class "Default")
      (node (ref "C21") (pin "1") (pinfunction "1_1") (pintype "passive"))
      (node (ref "C23") (pin "1") (pinfunction "1_1") (pintype "passive"))
      (node (ref "R20") (pin "1") (pinfunction "1_1") (pintype "passive"))
      (node (ref "U6") (pin "6") (pinfunction "VBACKUP_6") (pintype "bidirectional"))
    )
    (net (code "61") (name "Net-(U6-~{INT})") (class "Default")
      (node (ref "INT") (pin "TP") (pinfunction "TP_TP") (pintype "input"))
      (node (ref "U6") (pin "2") (pinfunction "~{INT}_2") (pintype "bidirectional"))
    )
    (net (code "62") (name "SPI0_CE0") (class "Default")
      (node (ref "CTRL1") (pin "5") (pinfunction "CSN_5") (pintype "passive"))
      (node (ref "K1") (pin "24") (pinfunction "24_24") (pintype "passive"))
    )
    (net (code "63") (name "SPI0_CE1") (class "Default")
      (node (ref "CTRL2") (pin "5") (pinfunction "CSN_5") (pintype "passive"))
      (node (ref "K1") (pin "26") (pinfunction "26_26") (pintype "passive"))
    )
    (net (code "64") (name "SPI0_MISO") (class "Default")
      (node (ref "CTRL1") (pin "4") (pinfunction "SDO_4") (pintype "passive"))
      (node (ref "CTRL2") (pin "4") (pinfunction "SDO_4") (pintype "passive"))
      (node (ref "K1") (pin "21") (pinfunction "21_21") (pintype "passive"))
    )
    (net (code "65") (name "SPI0_MOSI") (class "Default")
      (node (ref "CTRL1") (pin "7") (pinfunction "SDI_7") (pintype "passive"))
      (node (ref "CTRL2") (pin "7") (pinfunction "SDI_7") (pintype "passive"))
      (node (ref "K1") (pin "19") (pinfunction "19_19") (pintype "passive"))
    )
    (net (code "66") (name "SPI0_SCLK") (class "Default")
      (node (ref "CTRL1") (pin "6") (pinfunction "SCK_6") (pintype "passive"))
      (node (ref "CTRL2") (pin "6") (pinfunction "SCK_6") (pintype "passive"))
      (node (ref "K1") (pin "23") (pinfunction "23_23") (pintype "passive"))
    )
    (net (code "67") (name "SW") (class "Default")
      (node (ref "L1") (pin "1") (pinfunction "1_1") (pintype "passive"))
      (node (ref "R8") (pin "1") (pinfunction "1_1") (pintype "passive"))
      (node (ref "U3") (pin "8") (pinfunction "SW_8") (pintype "output"))
    )
    (net (code "68") (name "UART_RX") (class "Default")
      (node (ref "K1") (pin "10") (pinfunction "10_10") (pintype "passive"))
    )
    (net (code "69") (name "UART_TX") (class "Default")
      (node (ref "K1") (pin "8") (pinfunction "8_8") (pintype "passive"))
    )
    (net (code "70") (name "unconnected-(CTRL1-DIR-Pad1)") (class "Default")
      (node (ref "CTRL1") (pin "1") (pinfunction "DIR_1") (pintype "passive"))
    )
    (net (code "71") (name "unconnected-(CTRL1-STEP-Pad2)") (class "Default")
      (node (ref "CTRL1") (pin "2") (pinfunction "STEP_2") (pintype "passive"))
    )
    (net (code "72") (name "unconnected-(CTRL2-DIR-Pad1)") (class "Default")
      (node (ref "CTRL2") (pin "1") (pinfunction "DIR_1") (pintype "passive"))
    )
    (net (code "73") (name "unconnected-(CTRL2-STEP-Pad2)") (class "Default")
      (node (ref "CTRL2") (pin "2") (pinfunction "STEP_2") (pintype "passive"))
    )
    (net (code "74") (name "unconnected-(FAN-PadRPM)") (class "Default")
      (node (ref "FAN") (pin "RPM") (pinfunction "RPM_RPM") (pintype "passive"))
    )
    (net (code "75") (name "unconnected-(K1-Pad1)") (class "Default")
      (node (ref "K1") (pin "1") (pinfunction "1_1") (pintype "passive"))
    )
    (net (code "76") (name "unconnected-(U2-NC-PadB1)") (class "Default")
      (node (ref "U2") (pin "B1") (pinfunction "NC_B1") (pintype "passive"))
    )
  )
)
